# finalpcb_tz12_fp10.net
KiCad netlist of a schematic drawn in EAGLE
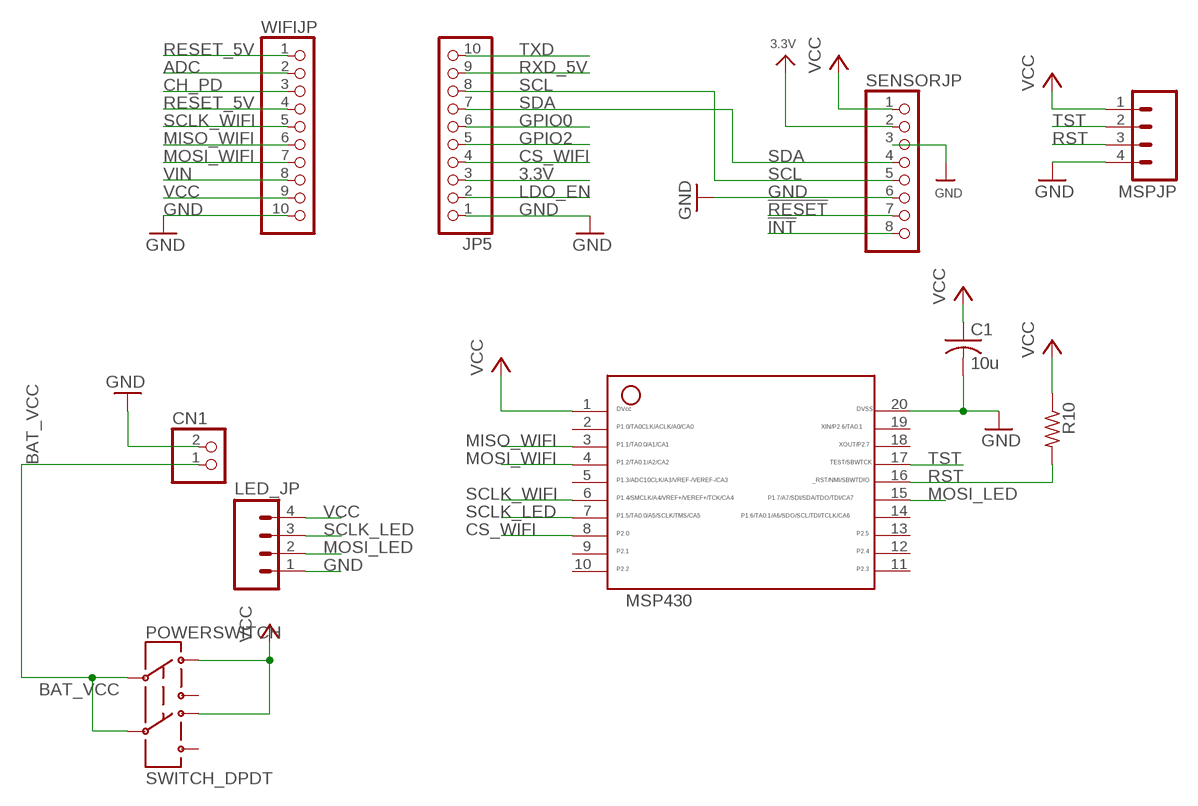
[diagram p0: schematic, sheet 1]

(export (version "E")
  (design (tool "Eeschema 10.0.6"))
  (components
    (comp (ref "C1")
      (value "10u")
      (footprint "eagle-import:C1206")
      (libsource (lib "eagle-import") (part "C-USC1206"))
    )
    (comp (ref "CN1")
      (value "JST_2PIN-SMT-RA")
      (footprint "eagle-import:JST-PH-2-SMT-RA")
      (libsource (lib "eagle-import") (part "JST_2PIN-SMT-RA"))
    )
    (comp (ref "JP5")
      (value "HEADER-1X1070MIL")
      (footprint "eagle-import:1X10_ROUND70")
      (libsource (lib "eagle-import") (part "HEADER-1X1070MIL"))
    )
    (comp (ref "LED_JP")
      (value "PENDANT_M04LOCK")
      (footprint "eagle-import:PENDANT_1X04_LOCK")
      (libsource (lib "eagle-import") (part "PENDANT_M04LOCK"))
    )
    (comp (ref "MSP430")
      (value "RATDBS_MSP430")
      (footprint "eagle-import:RATDBS_20_PIN")
      (libsource (lib "eagle-import") (part "RATDBS_MSP430"))
    )
    (comp (ref "MSPJP")
      (value "PENDANT_M04LOCK")
      (footprint "eagle-import:PENDANT_1X04_LOCK")
      (libsource (lib "eagle-import") (part "PENDANT_M04LOCK"))
    )
    (comp (ref "POWERSWITCH")
      (value "SWITCH_DPDT")
      (footprint "eagle-import:JS_DPDT_TH")
      (libsource (lib "eagle-import") (part "SWITCH_DPDT"))
    )
    (comp (ref "R10")
      (value "R-US_R1206")
      (footprint "eagle-import:R1206")
      (libsource (lib "eagle-import") (part "R-US_R1206"))
    )
    (comp (ref "SENSORJP")
      (value "HEADER-1X870MIL")
      (footprint "eagle-import:1X08_ROUND_70")
      (libsource (lib "eagle-import") (part "HEADER-1X870MIL"))
    )
    (comp (ref "WIFIJP")
      (value "HEADER-1X1070MIL")
      (footprint "eagle-import:1X10_ROUND70")
      (libsource (lib "eagle-import") (part "HEADER-1X1070MIL"))
    )
  )
  (nets
    (net (code "1") (name "/ADC") (class "Default")
      (node (ref "WIFIJP") (pin "2") (pinfunction "2_2") (pintype "passive"))
    )
    (net (code "2") (name "/BAT_VCC") (class "Default")
      (node (ref "CN1") (pin "1") (pinfunction "2_1") (pintype "passive"))
      (node (ref "POWERSWITCH") (pin "2") (pinfunction "2_2") (pintype "bidirectional"))
      (node (ref "POWERSWITCH") (pin "5") (pinfunction "5_5") (pintype "bidirectional"))
    )
    (net (code "3") (name "/CH_PD") (class "Default")
      (node (ref "WIFIJP") (pin "3") (pinfunction "3_3") (pintype "passive"))
    )
    (net (code "4") (name "/CS_WIFI") (class "Default")
      (node (ref "JP5") (pin "4") (pinfunction "4_4") (pintype "passive"))
      (node (ref "MSP430") (pin "8") (pinfunction "8_8") (pintype "bidirectional"))
    )
    (net (code "5") (name "/GPIO0") (class "Default")
      (node (ref "JP5") (pin "6") (pinfunction "6_6") (pintype "passive"))
    )
    (net (code "6") (name "/GPIO2") (class "Default")
      (node (ref "JP5") (pin "5") (pinfunction "5_5") (pintype "passive"))
    )
    (net (code "7") (name "/LDO_EN") (class "Default")
      (node (ref "JP5") (pin "2") (pinfunction "2_2") (pintype "passive"))
    )
    (net (code "8") (name "/MISO_WIFI") (class "Default")
      (node (ref "MSP430") (pin "3") (pinfunction "3_3") (pintype "bidirectional"))
      (node (ref "WIFIJP") (pin "6") (pinfunction "6_6") (pintype "passive"))
    )
    (net (code "9") (name "/MOSI_LED") (class "Default")
      (node (ref "LED_JP") (pin "2") (pinfunction "2_2") (pintype "passive"))
      (node (ref "MSP430") (pin "15") (pinfunction "15_15") (pintype "bidirectional"))
    )
    (net (code "10") (name "/MOSI_WIFI") (class "Default")
      (node (ref "MSP430") (pin "4") (pinfunction "4_4") (pintype "bidirectional"))
      (node (ref "WIFIJP") (pin "7") (pinfunction "7_7") (pintype "passive"))
    )
    (net (code "11") (name "/RESET_5V") (class "Default")
      (node (ref "WIFIJP") (pin "1") (pinfunction "1_1") (pintype "passive"))
      (node (ref "WIFIJP") (pin "4") (pinfunction "4_4") (pintype "passive"))
    )
    (net (code "12") (name "/RST") (class "Default")
      (node (ref "MSP430") (pin "16") (pinfunction "16_16") (pintype "bidirectional"))
      (node (ref "MSPJP") (pin "3") (pinfunction "3_3") (pintype "passive"))
      (node (ref "R10") (pin "2") (pinfunction "2_2") (pintype "passive"))
    )
    (net (code "13") (name "/RXD_5V") (class "Default")
      (node (ref "JP5") (pin "9") (pinfunction "9_9") (pintype "passive"))
    )
    (net (code "14") (name "/SCL") (class "Default")
      (node (ref "JP5") (pin "8") (pinfunction "8_8") (pintype "passive"))
      (node (ref "SENSORJP") (pin "5") (pinfunction "5_5") (pintype "passive"))
    )
    (net (code "15") (name "/SCLK_LED") (class "Default")
      (node (ref "LED_JP") (pin "3") (pinfunction "3_3") (pintype "passive"))
      (node (ref "MSP430") (pin "7") (pinfunction "7_7") (pintype "bidirectional"))
    )
    (net (code "16") (name "/SCLK_WIFI") (class "Default")
      (node (ref "MSP430") (pin "6") (pinfunction "6_6") (pintype "bidirectional"))
      (node (ref "WIFIJP") (pin "5") (pinfunction "5_5") (pintype "passive"))
    )
    (net (code "17") (name "/SDA") (class "Default")
      (node (ref "JP5") (pin "7") (pinfunction "7_7") (pintype "passive"))
      (node (ref "SENSORJP") (pin "4") (pinfunction "4_4") (pintype "passive"))
    )
    (net (code "18") (name "/TST") (class "Default")
      (node (ref "MSP430") (pin "17") (pinfunction "17_17") (pintype "bidirectional"))
      (node (ref "MSPJP") (pin "2") (pinfunction "2_2") (pintype "passive"))
    )
    (net (code "19") (name "/TXD") (class "Default")
      (node (ref "JP5") (pin "10") (pinfunction "10_10") (pintype "passive"))
    )
    (net (code "20") (name "/VIN") (class "Default")
      (node (ref "WIFIJP") (pin "8") (pinfunction "8_8") (pintype "passive"))
    )
    (net (code "21") (name "/~{INT}") (class "Default")
      (node (ref "SENSORJP") (pin "8") (pinfunction "8_8") (pintype "passive"))
    )
    (net (code "22") (name "/~{RESET}") (class "Default")
      (node (ref "SENSORJP") (pin "7") (pinfunction "7_7") (pintype "passive"))
    )
    (net (code "23") (name "3.3V") (class "Default")
      (node (ref "JP5") (pin "3") (pinfunction "3_3") (pintype "passive"))
      (node (ref "SENSORJP") (pin "2") (pinfunction "2_2") (pintype "passive"))
    )
    (net (code "24") (name "GND") (class "Default")
      (node (ref "C1") (pin "2") (pinfunction "2_2") (pintype "passive"))
      (node (ref "CN1") (pin "2") (pinfunction "1_2") (pintype "passive"))
      (node (ref "JP5") (pin "1") (pinfunction "1_1") (pintype "passive"))
      (node (ref "LED_JP") (pin "1") (pinfunction "1_1") (pintype "passive"))
      (node (ref "MSP430") (pin "20") (pinfunction "20_20") (pintype "bidirectional"))
      (node (ref "MSPJP") (pin "4") (pinfunction "4_4") (pintype "passive"))
      (node (ref "SENSORJP") (pin "3") (pinfunction "3_3") (pintype "passive"))
      (node (ref "SENSORJP") (pin "6") (pinfunction "6_6") (pintype "passive"))
      (node (ref "WIFIJP") (pin "10") (pinfunction "10_10") (pintype "passive"))
    )
    (net (code "25") (name "VCC") (class "Default")
      (node (ref "C1") (pin "1") (pinfunction "1_1") (pintype "passive"))
      (node (ref "LED_JP") (pin "4") (pinfunction "4_4") (pintype "passive"))
      (node (ref "MSP430") (pin "1") (pinfunction "1_1") (pintype "bidirectional"))
      (node (ref "MSPJP") (pin "1") (pinfunction "1_1") (pintype "passive"))
      (node (ref "POWERSWITCH") (pin "1") (pinfunction "1_1") (pintype "bidirectional"))
      (node (ref "POWERSWITCH") (pin "4") (pinfunction "4_4") (pintype "bidirectional"))
      (node (ref "R10") (pin "1") (pinfunction "1_1") (pintype "passive"))
      (node (ref "SENSORJP") (pin "1") (pinfunction "1_1") (pintype "passive"))
      (node (ref "WIFIJP") (pin "9") (pinfunction "9_9") (pintype "passive"))
    )
    (net (code "26") (name "unconnected-(MSP430-Pad2)") (class "Default")
      (node (ref "MSP430") (pin "2") (pinfunction "2_2") (pintype "bidirectional"))
    )
    (net (code "27") (name "unconnected-(MSP430-Pad5)") (class "Default")
      (node (ref "MSP430") (pin "5") (pinfunction "5_5") (pintype "bidirectional"))
    )
    (net (code "28") (name "unconnected-(MSP430-Pad9)") (class "Default")
      (node (ref "MSP430") (pin "9") (pinfunction "9_9") (pintype "bidirectional"))
    )
    (net (code "29") (name "unconnected-(MSP430-Pad10)") (class "Default")
      (node (ref "MSP430") (pin "10") (pinfunction "10_10") (pintype "bidirectional"))
    )
    (net (code "30") (name "unconnected-(MSP430-Pad11)") (class "Default")
      (node (ref "MSP430") (pin "11") (pinfunction "11_11") (pintype "bidirectional"))
    )
    (net (code "31") (name "unconnected-(MSP430-Pad12)") (class "Default")
      (node (ref "MSP430") (pin "12") (pinfunction "12_12") (pintype "bidirectional"))
    )
    (net (code "32") (name "unconnected-(MSP430-Pad13)") (class "Default")
      (node (ref "MSP430") (pin "13") (pinfunction "13_13") (pintype "bidirectional"))
    )
    (net (code "33") (name "unconnected-(MSP430-Pad14)") (class "Default")
      (node (ref "MSP430") (pin "14") (pinfunction "14_14") (pintype "bidirectional"))
    )
    (net (code "34") (name "unconnected-(MSP430-Pad18)") (class "Default")
      (node (ref "MSP430") (pin "18") (pinfunction "18_18") (pintype "bidirectional"))
    )
    (net (code "35") (name "unconnected-(MSP430-Pad19)") (class "Default")
      (node (ref "MSP430") (pin "19") (pinfunction "19_19") (pintype "bidirectional"))
    )
    (net (code "36") (name "unconnected-(POWERSWITCH-Pad3)") (class "Default")
      (node (ref "POWERSWITCH") (pin "3") (pinfunction "3_3") (pintype "bidirectional"))
    )
    (net (code "37") (name "unconnected-(POWERSWITCH-Pad6)") (class "Default")
      (node (ref "POWERSWITCH") (pin "6") (pinfunction "6_6") (pintype "bidirectional"))
    )
  )
)
